# Lightpack6_0L.net
KiCad netlist of a schematic drawn in EAGLE
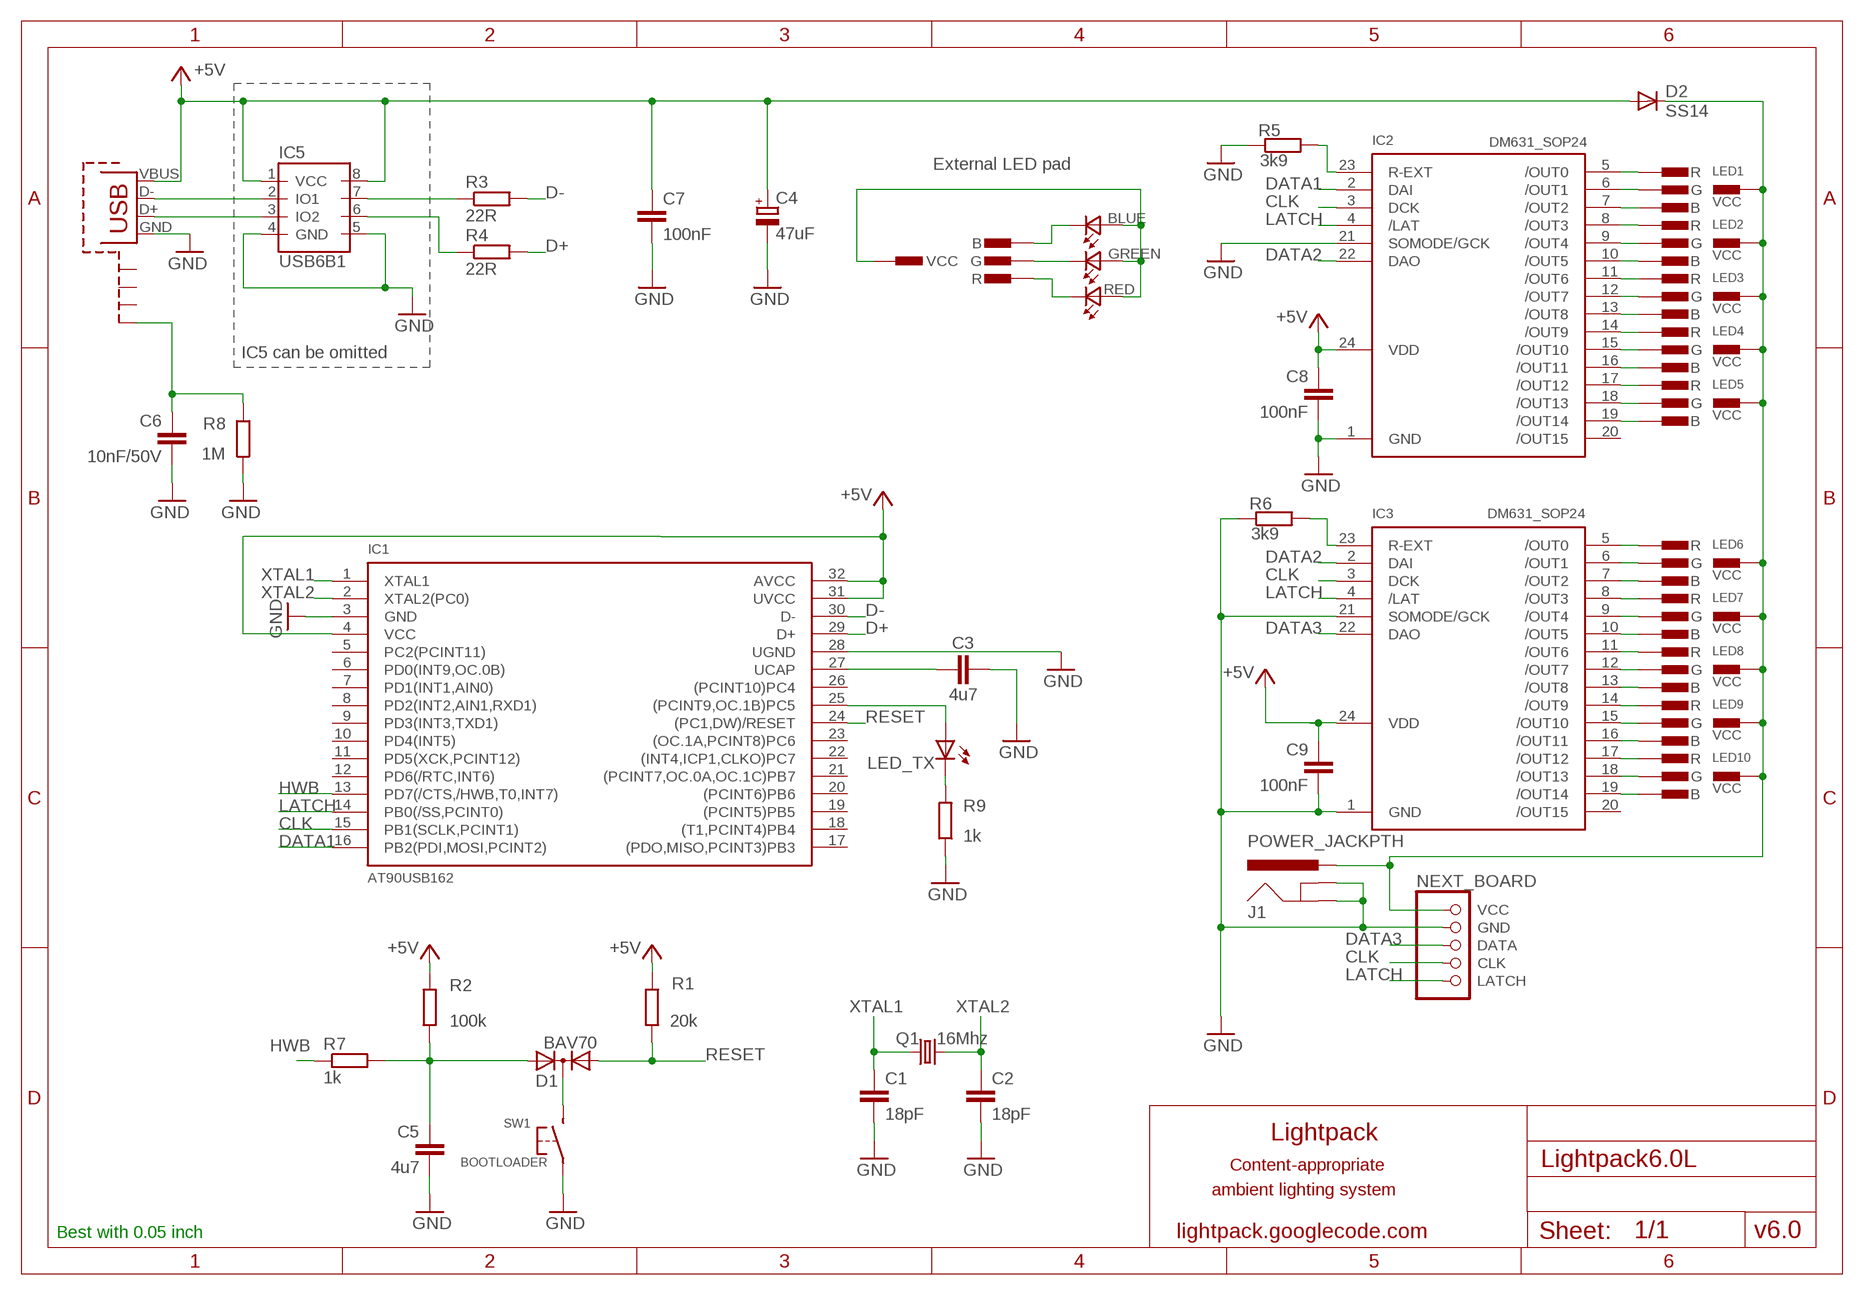
[diagram p0: schematic, sheet 1]

(export (version "E")
  (design (tool "Eeschema 10.0.6"))
  (components
    (comp (ref "C1")
      (value "18pF")
      (footprint "eagle-import:C1206")
      (libsource (lib "eagle-import") (part "C-EUC1206"))
    )
    (comp (ref "C2")
      (value "18pF")
      (footprint "eagle-import:C1206")
      (libsource (lib "eagle-import") (part "C-EUC1206"))
    )
    (comp (ref "C3")
      (value "4u7")
      (footprint "eagle-import:C1206")
      (libsource (lib "eagle-import") (part "C-EUC1206"))
    )
    (comp (ref "C4")
      (value "47uF")
      (footprint "eagle-import:D_7343-31W")
      (libsource (lib "eagle-import") (part "CPOL-EUD/7343-31W"))
    )
    (comp (ref "C5")
      (value "4u7")
      (footprint "eagle-import:C1206")
      (libsource (lib "eagle-import") (part "C-EUC1206"))
    )
    (comp (ref "C6")
      (value "10nF/50V")
      (footprint "eagle-import:C1206")
      (libsource (lib "eagle-import") (part "C-EUC1206"))
    )
    (comp (ref "C7")
      (value "100nF")
      (footprint "eagle-import:C1206")
      (libsource (lib "eagle-import") (part "C-EUC1206"))
    )
    (comp (ref "C8")
      (value "100nF")
      (footprint "eagle-import:C1206")
      (libsource (lib "eagle-import") (part "C-EUC1206"))
    )
    (comp (ref "C9")
      (value "100nF")
      (footprint "eagle-import:C1206")
      (libsource (lib "eagle-import") (part "C-EUC1206"))
    )
    (comp (ref "D1")
      (value "BAV70")
      (footprint "eagle-import:SOT23")
      (libsource (lib "eagle-import") (part "DIODE-2AC|CASOT23"))
    )
    (comp (ref "D2")
      (value "SS14")
      (footprint "eagle-import:SMB")
      (libsource (lib "eagle-import") (part "DIODE-SMB"))
    )
    (comp (ref "EXT_LED")
      (value "TOPLED-3RF-W2SA50TS")
      (footprint "eagle-import:LP2C63-ST-RGB-SR0")
      (libsource (lib "eagle-import") (part "TOPLED-3RF-W2SA50TS"))
    )
    (comp (ref "IC1")
      (value "AT90USB162")
      (footprint "eagle-import:TQFP32")
      (libsource (lib "eagle-import") (part "AT90USB162"))
    )
    (comp (ref "IC2")
      (value "DM631_SOP24")
      (footprint "eagle-import:SOP24-300-1.27")
      (libsource (lib "eagle-import") (part "DM631_SOP24"))
    )
    (comp (ref "IC3")
      (value "DM631_SOP24")
      (footprint "eagle-import:SOP24-300-1.27")
      (libsource (lib "eagle-import") (part "DM631_SOP24"))
    )
    (comp (ref "IC5")
      (value "USB6B1")
      (footprint "eagle-import:SO08")
      (libsource (lib "eagle-import") (part "USB6B1"))
    )
    (comp (ref "J1")
      (value "POWER_JACKPTH")
      (footprint "eagle-import:POWER_JACK_PTH")
      (libsource (lib "eagle-import") (part "POWER_JACKPTH"))
    )
    (comp (ref "LED1")
      (value "CON-RGB-LED")
      (footprint "eagle-import:CON-RGB-LED")
      (libsource (lib "eagle-import") (part "CON-RGB-LED"))
    )
    (comp (ref "LED2")
      (value "CON-RGB-LED")
      (footprint "eagle-import:CON-RGB-LED")
      (libsource (lib "eagle-import") (part "CON-RGB-LED"))
    )
    (comp (ref "LED3")
      (value "CON-RGB-LED")
      (footprint "eagle-import:CON-RGB-LED")
      (libsource (lib "eagle-import") (part "CON-RGB-LED"))
    )
    (comp (ref "LED4")
      (value "CON-RGB-LEDVCC-INDENT")
      (footprint "eagle-import:CON-RGB-LED-WITH-VCC-INDENT")
      (libsource (lib "eagle-import") (part "CON-RGB-LEDVCC-INDENT"))
    )
    (comp (ref "LED5")
      (value "CON-RGB-LEDVCC-INDENT")
      (footprint "eagle-import:CON-RGB-LED-WITH-VCC-INDENT")
      (libsource (lib "eagle-import") (part "CON-RGB-LEDVCC-INDENT"))
    )
    (comp (ref "LED6")
      (value "CON-RGB-LED")
      (footprint "eagle-import:CON-RGB-LED")
      (libsource (lib "eagle-import") (part "CON-RGB-LED"))
    )
    (comp (ref "LED7")
      (value "CON-RGB-LED")
      (footprint "eagle-import:CON-RGB-LED")
      (libsource (lib "eagle-import") (part "CON-RGB-LED"))
    )
    (comp (ref "LED8")
      (value "CON-RGB-LED")
      (footprint "eagle-import:CON-RGB-LED")
      (libsource (lib "eagle-import") (part "CON-RGB-LED"))
    )
    (comp (ref "LED9")
      (value "CON-RGB-LED")
      (footprint "eagle-import:CON-RGB-LED")
      (libsource (lib "eagle-import") (part "CON-RGB-LED"))
    )
    (comp (ref "LED10")
      (value "CON-RGB-LED")
      (footprint "eagle-import:CON-RGB-LED")
      (libsource (lib "eagle-import") (part "CON-RGB-LED"))
    )
    (comp (ref "LED12")
      (value "CON-RGB-LED\"")
      (footprint "eagle-import:CON-RGB-LED")
      (libsource (lib "eagle-import") (part "CON-RGB-LED{dblquote}"))
    )
    (comp (ref "LED_TX")
      (value "GREEN")
      (footprint "eagle-import:CHIPLED_0805")
      (libsource (lib "eagle-import") (part "LEDCHIPLED_0805"))
    )
    (comp (ref "NEXT_BOARD")
      (value "LED_DRIVER_BOARD")
      (footprint "eagle-import:DATA-CLK-LATCH")
      (libsource (lib "eagle-import") (part "LED_DRIVER_BOARD"))
    )
    (comp (ref "Q1")
      (value "16Mhz")
      (footprint "eagle-import:HC49UP")
      (libsource (lib "eagle-import") (part "CRYSTALHC49UP"))
    )
    (comp (ref "R1")
      (value "20k")
      (footprint "eagle-import:R1206")
      (libsource (lib "eagle-import") (part "R-EU_R1206"))
    )
    (comp (ref "R2")
      (value "100k")
      (footprint "eagle-import:R1206")
      (libsource (lib "eagle-import") (part "R-EU_R1206_2"))
    )
    (comp (ref "R3")
      (value "22R")
      (footprint "eagle-import:R1206")
      (libsource (lib "eagle-import") (part "rcl_R-EU_R1206"))
    )
    (comp (ref "R4")
      (value "22R")
      (footprint "eagle-import:R1206")
      (libsource (lib "eagle-import") (part "rcl_R-EU_R1206"))
    )
    (comp (ref "R5")
      (value "3k9")
      (footprint "eagle-import:R1206")
      (libsource (lib "eagle-import") (part "R-EU_R1206"))
    )
    (comp (ref "R6")
      (value "3k9")
      (footprint "eagle-import:R1206")
      (libsource (lib "eagle-import") (part "R-EU_R1206"))
    )
    (comp (ref "R7")
      (value "1k")
      (footprint "eagle-import:R1206")
      (libsource (lib "eagle-import") (part "rcl_R-EU_R1206"))
    )
    (comp (ref "R8")
      (value "1M")
      (footprint "eagle-import:R1206")
      (libsource (lib "eagle-import") (part "rcl_R-EU_R1206"))
    )
    (comp (ref "R9")
      (value "1k")
      (footprint "eagle-import:R1206")
      (libsource (lib "eagle-import") (part "rcl_R-EU_R1206"))
    )
    (comp (ref "SW1")
      (value "BOOTLOADER")
      (footprint "eagle-import:BUTTON-SMD")
      (libsource (lib "eagle-import") (part "BUTTON"))
    )
    (comp (ref "X1")
      (value "USB-MB-S")
      (footprint "eagle-import:USB-MB-S")
      (libsource (lib "eagle-import") (part "USB-MB-S"))
    )
  )
  (nets
    (net (code "1") (name "+5V") (class "Default")
      (node (ref "C4") (pin "+") (pinfunction "+_+") (pintype "passive"))
      (node (ref "C7") (pin "1") (pinfunction "1_1") (pintype "passive"))
      (node (ref "C8") (pin "1") (pinfunction "1_1") (pintype "passive"))
      (node (ref "C9") (pin "1") (pinfunction "1_1") (pintype "passive"))
      (node (ref "D2") (pin "A") (pinfunction "A_A") (pintype "passive"))
      (node (ref "IC1") (pin "31") (pinfunction "UVCC_31") (pintype "bidirectional"))
      (node (ref "IC1") (pin "32") (pinfunction "AVCC_32") (pintype "bidirectional"))
      (node (ref "IC1") (pin "4") (pinfunction "VCC_4") (pintype "bidirectional"))
      (node (ref "IC2") (pin "24") (pinfunction "VDD_24") (pintype "bidirectional"))
      (node (ref "IC3") (pin "24") (pinfunction "VDD_24") (pintype "bidirectional"))
      (node (ref "IC5") (pin "1") (pinfunction "VCC_1") (pintype "power_in"))
      (node (ref "IC5") (pin "8") (pinfunction "VCC_8") (pintype "power_in"))
      (node (ref "R1") (pin "2") (pinfunction "2_2") (pintype "passive"))
      (node (ref "R2") (pin "1") (pinfunction "2_1") (pintype "passive"))
      (node (ref "X1") (pin "VBUS") (pinfunction "VBUS_VBUS") (pintype "bidirectional"))
    )
    (net (code "2") (name "/CLK") (class "Default")
      (node (ref "IC1") (pin "15") (pinfunction "PB1(SCLK,PCINT1)_15") (pintype "bidirectional"))
      (node (ref "IC2") (pin "3") (pinfunction "DCK_3") (pintype "bidirectional"))
      (node (ref "IC3") (pin "3") (pinfunction "DCK_3") (pintype "bidirectional"))
      (node (ref "NEXT_BOARD") (pin "CLK") (pinfunction "CLK_CLK") (pintype "passive"))
    )
    (net (code "3") (name "/D+") (class "Default")
      (node (ref "IC1") (pin "29") (pinfunction "D+_29") (pintype "bidirectional"))
      (node (ref "R4") (pin "2") (pinfunction "2_2") (pintype "passive"))
    )
    (net (code "4") (name "/D-") (class "Default")
      (node (ref "IC1") (pin "30") (pinfunction "D-_30") (pintype "bidirectional"))
      (node (ref "R3") (pin "2") (pinfunction "2_2") (pintype "passive"))
    )
    (net (code "5") (name "/DATA1") (class "Default")
      (node (ref "IC1") (pin "16") (pinfunction "PB2(PDI,MOSI,PCINT2)_16") (pintype "bidirectional"))
      (node (ref "IC2") (pin "2") (pinfunction "DAI_2") (pintype "bidirectional"))
    )
    (net (code "6") (name "/DATA2") (class "Default")
      (node (ref "IC2") (pin "22") (pinfunction "DAO_22") (pintype "bidirectional"))
      (node (ref "IC3") (pin "2") (pinfunction "DAI_2") (pintype "bidirectional"))
    )
    (net (code "7") (name "/DATA3") (class "Default")
      (node (ref "IC3") (pin "22") (pinfunction "DAO_22") (pintype "bidirectional"))
      (node (ref "NEXT_BOARD") (pin "DATA") (pinfunction "DATA_DATA") (pintype "passive"))
    )
    (net (code "8") (name "/HWB") (class "Default")
      (node (ref "IC1") (pin "13") (pinfunction "PD7(/CTS,/HWB,T0,INT7)_13") (pintype "bidirectional"))
      (node (ref "R7") (pin "1") (pinfunction "1_1") (pintype "passive"))
    )
    (net (code "9") (name "/LATCH") (class "Default")
      (node (ref "IC1") (pin "14") (pinfunction "PB0(/SS,PCINT0)_14") (pintype "bidirectional"))
      (node (ref "IC2") (pin "4") (pinfunction "/LAT_4") (pintype "bidirectional"))
      (node (ref "IC3") (pin "4") (pinfunction "/LAT_4") (pintype "bidirectional"))
      (node (ref "NEXT_BOARD") (pin "LATCH") (pinfunction "LATCH_LATCH") (pintype "passive"))
    )
    (net (code "10") (name "/RESET") (class "Default")
      (node (ref "D1") (pin "1") (pinfunction "A1_1") (pintype "passive"))
      (node (ref "IC1") (pin "24") (pinfunction "(PC1,DW)/RESET_24") (pintype "bidirectional"))
      (node (ref "R1") (pin "1") (pinfunction "1_1") (pintype "passive"))
    )
    (net (code "11") (name "/XTAL1") (class "Default")
      (node (ref "C1") (pin "1") (pinfunction "1_1") (pintype "passive"))
      (node (ref "IC1") (pin "1") (pinfunction "XTAL1_1") (pintype "bidirectional"))
      (node (ref "Q1") (pin "1") (pinfunction "1_1") (pintype "passive"))
    )
    (net (code "12") (name "/XTAL2") (class "Default")
      (node (ref "C2") (pin "1") (pinfunction "1_1") (pintype "passive"))
      (node (ref "IC1") (pin "2") (pinfunction "XTAL2(PC0)_2") (pintype "bidirectional"))
      (node (ref "Q1") (pin "2") (pinfunction "2_2") (pintype "passive"))
    )
    (net (code "13") (name "GND") (class "Default")
      (node (ref "C1") (pin "2") (pinfunction "2_2") (pintype "passive"))
      (node (ref "C2") (pin "2") (pinfunction "2_2") (pintype "passive"))
      (node (ref "C3") (pin "1") (pinfunction "1_1") (pintype "passive"))
      (node (ref "C4") (pin "-") (pinfunction "-_-") (pintype "passive"))
      (node (ref "C5") (pin "2") (pinfunction "2_2") (pintype "passive"))
      (node (ref "C6") (pin "2") (pinfunction "2_2") (pintype "passive"))
      (node (ref "C7") (pin "2") (pinfunction "2_2") (pintype "passive"))
      (node (ref "C8") (pin "2") (pinfunction "2_2") (pintype "passive"))
      (node (ref "C9") (pin "2") (pinfunction "2_2") (pintype "passive"))
      (node (ref "IC1") (pin "28") (pinfunction "UGND_28") (pintype "bidirectional"))
      (node (ref "IC1") (pin "3") (pinfunction "GND_3") (pintype "bidirectional"))
      (node (ref "IC2") (pin "1") (pinfunction "GND_1") (pintype "bidirectional"))
      (node (ref "IC2") (pin "21") (pinfunction "SOMODE/GCK_21") (pintype "bidirectional"))
      (node (ref "IC3") (pin "1") (pinfunction "GND_1") (pintype "bidirectional"))
      (node (ref "IC3") (pin "21") (pinfunction "SOMODE/GCK_21") (pintype "bidirectional"))
      (node (ref "IC5") (pin "4") (pinfunction "GND_4") (pintype "power_in"))
      (node (ref "IC5") (pin "5") (pinfunction "GND_5") (pintype "power_in"))
      (node (ref "J1") (pin "GND") (pinfunction "GND_GND") (pintype "bidirectional"))
      (node (ref "J1") (pin "GNDBREAK") (pinfunction "GNDBREAK_GNDBREAK") (pintype "bidirectional"))
      (node (ref "NEXT_BOARD") (pin "GND") (pinfunction "GND_GND") (pintype "passive"))
      (node (ref "R5") (pin "1") (pinfunction "1_1") (pintype "passive"))
      (node (ref "R6") (pin "1") (pinfunction "1_1") (pintype "passive"))
      (node (ref "R8") (pin "1") (pinfunction "1_1") (pintype "passive"))
      (node (ref "R9") (pin "1") (pinfunction "1_1") (pintype "passive"))
      (node (ref "SW1") (pin "1") (pinfunction "1_1") (pintype "passive"))
      (node (ref "X1") (pin "GND") (pinfunction "GND_GND") (pintype "bidirectional"))
    )
    (net (code "14") (name "Net-(C6-Pad1)") (class "Default")
      (node (ref "C6") (pin "1") (pinfunction "1_1") (pintype "passive"))
      (node (ref "R8") (pin "2") (pinfunction "2_2") (pintype "passive"))
      (node (ref "X1") (pin "SHIELD4") (pinfunction "SHIELD4_SHIELD4") (pintype "bidirectional"))
    )
    (net (code "15") (name "Net-(D1-A2)") (class "Default")
      (node (ref "C5") (pin "1") (pinfunction "1_1") (pintype "passive"))
      (node (ref "D1") (pin "2") (pinfunction "A2_2") (pintype "passive"))
      (node (ref "R2") (pin "2") (pinfunction "1_2") (pintype "passive"))
      (node (ref "R7") (pin "2") (pinfunction "2_2") (pintype "passive"))
    )
    (net (code "16") (name "Net-(D1-C)") (class "Default")
      (node (ref "D1") (pin "3") (pinfunction "C_3") (pintype "passive"))
      (node (ref "SW1") (pin "2") (pinfunction "2_2") (pintype "passive"))
    )
    (net (code "17") (name "Net-(D2-PadC)") (class "Default")
      (node (ref "D2") (pin "C") (pinfunction "C_C") (pintype "passive"))
      (node (ref "J1") (pin "PWR") (pinfunction "PWR_PWR") (pintype "bidirectional"))
      (node (ref "LED1") (pin "VCC") (pinfunction "VCC_VCC") (pintype "bidirectional"))
      (node (ref "LED10") (pin "VCC") (pinfunction "VCC_VCC") (pintype "bidirectional"))
      (node (ref "LED2") (pin "VCC") (pinfunction "VCC_VCC") (pintype "bidirectional"))
      (node (ref "LED3") (pin "VCC") (pinfunction "VCC_VCC") (pintype "bidirectional"))
      (node (ref "LED4") (pin "VCC") (pinfunction "VCC_VCC") (pintype "bidirectional"))
      (node (ref "LED5") (pin "VCC") (pinfunction "VCC_VCC") (pintype "bidirectional"))
      (node (ref "LED6") (pin "VCC") (pinfunction "VCC_VCC") (pintype "bidirectional"))
      (node (ref "LED7") (pin "VCC") (pinfunction "VCC_VCC") (pintype "bidirectional"))
      (node (ref "LED8") (pin "VCC") (pinfunction "VCC_VCC") (pintype "bidirectional"))
      (node (ref "LED9") (pin "VCC") (pinfunction "VCC_VCC") (pintype "bidirectional"))
      (node (ref "NEXT_BOARD") (pin "VCC") (pinfunction "VCC_VCC") (pintype "passive"))
    )
    (net (code "18") (name "Net-(EXT_LED-PadBLUE)") (class "Default")
      (node (ref "EXT_LED") (pin "BLUE") (pinfunction "BLUE_BLUE") (pintype "passive"))
      (node (ref "EXT_LED") (pin "GREEN") (pinfunction "GREEN_GREEN") (pintype "passive"))
      (node (ref "EXT_LED") (pin "RED") (pinfunction "RED_RED") (pintype "passive"))
      (node (ref "LED12") (pin "VCC") (pinfunction "VCC_VCC") (pintype "bidirectional"))
    )
    (net (code "19") (name "Net-(EXT_LED-PadCBLUE)") (class "Default")
      (node (ref "EXT_LED") (pin "CBLUE") (pinfunction "CBLUE_CBLUE") (pintype "passive"))
      (node (ref "LED12") (pin "B") (pinfunction "B_B") (pintype "bidirectional"))
    )
    (net (code "20") (name "Net-(EXT_LED-PadCGREEN)") (class "Default")
      (node (ref "EXT_LED") (pin "CGREEN") (pinfunction "CGREEN_CGREEN") (pintype "passive"))
      (node (ref "LED12") (pin "G") (pinfunction "G_G") (pintype "bidirectional"))
    )
    (net (code "21") (name "Net-(EXT_LED-PadCRED)") (class "Default")
      (node (ref "EXT_LED") (pin "CRED") (pinfunction "CRED_CRED") (pintype "passive"))
      (node (ref "LED12") (pin "R") (pinfunction "R_R") (pintype "bidirectional"))
    )
    (net (code "22") (name "Net-(IC1-(PCINT9,OC.1B)PC5)") (class "Default")
      (node (ref "IC1") (pin "25") (pinfunction "(PCINT9,OC.1B)PC5_25") (pintype "bidirectional"))
      (node (ref "LED_TX") (pin "A") (pinfunction "A_A") (pintype "passive"))
    )
    (net (code "23") (name "Net-(IC1-UCAP)") (class "Default")
      (node (ref "C3") (pin "2") (pinfunction "2_2") (pintype "passive"))
      (node (ref "IC1") (pin "27") (pinfunction "UCAP_27") (pintype "bidirectional"))
    )
    (net (code "24") (name "Net-(IC2-R-EXT)") (class "Default")
      (node (ref "IC2") (pin "23") (pinfunction "R-EXT_23") (pintype "bidirectional"))
      (node (ref "R5") (pin "2") (pinfunction "2_2") (pintype "passive"))
    )
    (net (code "25") (name "Net-(IC2-{slash}OUT0)") (class "Default")
      (node (ref "IC2") (pin "5") (pinfunction "/OUT0_5") (pintype "bidirectional"))
      (node (ref "LED1") (pin "R") (pinfunction "R_R") (pintype "bidirectional"))
    )
    (net (code "26") (name "Net-(IC2-{slash}OUT1)") (class "Default")
      (node (ref "IC2") (pin "6") (pinfunction "/OUT1_6") (pintype "bidirectional"))
      (node (ref "LED1") (pin "G") (pinfunction "G_G") (pintype "bidirectional"))
    )
    (net (code "27") (name "Net-(IC2-{slash}OUT2)") (class "Default")
      (node (ref "IC2") (pin "7") (pinfunction "/OUT2_7") (pintype "bidirectional"))
      (node (ref "LED1") (pin "B") (pinfunction "B_B") (pintype "bidirectional"))
    )
    (net (code "28") (name "Net-(IC2-{slash}OUT3)") (class "Default")
      (node (ref "IC2") (pin "8") (pinfunction "/OUT3_8") (pintype "bidirectional"))
      (node (ref "LED2") (pin "R") (pinfunction "R_R") (pintype "bidirectional"))
    )
    (net (code "29") (name "Net-(IC2-{slash}OUT4)") (class "Default")
      (node (ref "IC2") (pin "9") (pinfunction "/OUT4_9") (pintype "bidirectional"))
      (node (ref "LED2") (pin "G") (pinfunction "G_G") (pintype "bidirectional"))
    )
    (net (code "30") (name "Net-(IC2-{slash}OUT5)") (class "Default")
      (node (ref "IC2") (pin "10") (pinfunction "/OUT5_10") (pintype "bidirectional"))
      (node (ref "LED2") (pin "B") (pinfunction "B_B") (pintype "bidirectional"))
    )
    (net (code "31") (name "Net-(IC2-{slash}OUT6)") (class "Default")
      (node (ref "IC2") (pin "11") (pinfunction "/OUT6_11") (pintype "bidirectional"))
      (node (ref "LED3") (pin "R") (pinfunction "R_R") (pintype "bidirectional"))
    )
    (net (code "32") (name "Net-(IC2-{slash}OUT7)") (class "Default")
      (node (ref "IC2") (pin "12") (pinfunction "/OUT7_12") (pintype "bidirectional"))
      (node (ref "LED3") (pin "G") (pinfunction "G_G") (pintype "bidirectional"))
    )
    (net (code "33") (name "Net-(IC2-{slash}OUT8)") (class "Default")
      (node (ref "IC2") (pin "13") (pinfunction "/OUT8_13") (pintype "bidirectional"))
      (node (ref "LED3") (pin "B") (pinfunction "B_B") (pintype "bidirectional"))
    )
    (net (code "34") (name "Net-(IC2-{slash}OUT9)") (class "Default")
      (node (ref "IC2") (pin "14") (pinfunction "/OUT9_14") (pintype "bidirectional"))
      (node (ref "LED4") (pin "R") (pinfunction "R_R") (pintype "bidirectional"))
    )
    (net (code "35") (name "Net-(IC2-{slash}OUT10)") (class "Default")
      (node (ref "IC2") (pin "15") (pinfunction "/OUT10_15") (pintype "bidirectional"))
      (node (ref "LED4") (pin "G") (pinfunction "G_G") (pintype "bidirectional"))
    )
    (net (code "36") (name "Net-(IC2-{slash}OUT11)") (class "Default")
      (node (ref "IC2") (pin "16") (pinfunction "/OUT11_16") (pintype "bidirectional"))
      (node (ref "LED4") (pin "B") (pinfunction "B_B") (pintype "bidirectional"))
    )
    (net (code "37") (name "Net-(IC2-{slash}OUT12)") (class "Default")
      (node (ref "IC2") (pin "17") (pinfunction "/OUT12_17") (pintype "bidirectional"))
      (node (ref "LED5") (pin "R") (pinfunction "R_R") (pintype "bidirectional"))
    )
    (net (code "38") (name "Net-(IC2-{slash}OUT13)") (class "Default")
      (node (ref "IC2") (pin "18") (pinfunction "/OUT13_18") (pintype "bidirectional"))
      (node (ref "LED5") (pin "G") (pinfunction "G_G") (pintype "bidirectional"))
    )
    (net (code "39") (name "Net-(IC2-{slash}OUT14)") (class "Default")
      (node (ref "IC2") (pin "19") (pinfunction "/OUT14_19") (pintype "bidirectional"))
      (node (ref "LED5") (pin "B") (pinfunction "B_B") (pintype "bidirectional"))
    )
    (net (code "40") (name "Net-(IC3-R-EXT)") (class "Default")
      (node (ref "IC3") (pin "23") (pinfunction "R-EXT_23") (pintype "bidirectional"))
      (node (ref "R6") (pin "2") (pinfunction "2_2") (pintype "passive"))
    )
    (net (code "41") (name "Net-(IC3-{slash}OUT0)") (class "Default")
      (node (ref "IC3") (pin "5") (pinfunction "/OUT0_5") (pintype "bidirectional"))
      (node (ref "LED6") (pin "R") (pinfunction "R_R") (pintype "bidirectional"))
    )
    (net (code "42") (name "Net-(IC3-{slash}OUT1)") (class "Default")
      (node (ref "IC3") (pin "6") (pinfunction "/OUT1_6") (pintype "bidirectional"))
      (node (ref "LED6") (pin "G") (pinfunction "G_G") (pintype "bidirectional"))
    )
    (net (code "43") (name "Net-(IC3-{slash}OUT2)") (class "Default")
      (node (ref "IC3") (pin "7") (pinfunction "/OUT2_7") (pintype "bidirectional"))
      (node (ref "LED6") (pin "B") (pinfunction "B_B") (pintype "bidirectional"))
    )
    (net (code "44") (name "Net-(IC3-{slash}OUT3)") (class "Default")
      (node (ref "IC3") (pin "8") (pinfunction "/OUT3_8") (pintype "bidirectional"))
      (node (ref "LED7") (pin "R") (pinfunction "R_R") (pintype "bidirectional"))
    )
    (net (code "45") (name "Net-(IC3-{slash}OUT4)") (class "Default")
      (node (ref "IC3") (pin "9") (pinfunction "/OUT4_9") (pintype "bidirectional"))
      (node (ref "LED7") (pin "G") (pinfunction "G_G") (pintype "bidirectional"))
    )
    (net (code "46") (name "Net-(IC3-{slash}OUT5)") (class "Default")
      (node (ref "IC3") (pin "10") (pinfunction "/OUT5_10") (pintype "bidirectional"))
      (node (ref "LED7") (pin "B") (pinfunction "B_B") (pintype "bidirectional"))
    )
    (net (code "47") (name "Net-(IC3-{slash}OUT6)") (class "Default")
      (node (ref "IC3") (pin "11") (pinfunction "/OUT6_11") (pintype "bidirectional"))
      (node (ref "LED8") (pin "R") (pinfunction "R_R") (pintype "bidirectional"))
    )
    (net (code "48") (name "Net-(IC3-{slash}OUT7)") (class "Default")
      (node (ref "IC3") (pin "12") (pinfunction "/OUT7_12") (pintype "bidirectional"))
      (node (ref "LED8") (pin "G") (pinfunction "G_G") (pintype "bidirectional"))
    )
    (net (code "49") (name "Net-(IC3-{slash}OUT8)") (class "Default")
      (node (ref "IC3") (pin "13") (pinfunction "/OUT8_13") (pintype "bidirectional"))
      (node (ref "LED8") (pin "B") (pinfunction "B_B") (pintype "bidirectional"))
    )
    (net (code "50") (name "Net-(IC3-{slash}OUT9)") (class "Default")
      (node (ref "IC3") (pin "14") (pinfunction "/OUT9_14") (pintype "bidirectional"))
      (node (ref "LED9") (pin "R") (pinfunction "R_R") (pintype "bidirectional"))
    )
    (net (code "51") (name "Net-(IC3-{slash}OUT10)") (class "Default")
      (node (ref "IC3") (pin "15") (pinfunction "/OUT10_15") (pintype "bidirectional"))
      (node (ref "LED9") (pin "G") (pinfunction "G_G") (pintype "bidirectional"))
    )
    (net (code "52") (name "Net-(IC3-{slash}OUT11)") (class "Default")
      (node (ref "IC3") (pin "16") (pinfunction "/OUT11_16") (pintype "bidirectional"))
      (node (ref "LED9") (pin "B") (pinfunction "B_B") (pintype "bidirectional"))
    )
    (net (code "53") (name "Net-(IC3-{slash}OUT12)") (class "Default")
      (node (ref "IC3") (pin "17") (pinfunction "/OUT12_17") (pintype "bidirectional"))
      (node (ref "LED10") (pin "R") (pinfunction "R_R") (pintype "bidirectional"))
    )
    (net (code "54") (name "Net-(IC3-{slash}OUT13)") (class "Default")
      (node (ref "IC3") (pin "18") (pinfunction "/OUT13_18") (pintype "bidirectional"))
      (node (ref "LED10") (pin "G") (pinfunction "G_G") (pintype "bidirectional"))
    )
    (net (code "55") (name "Net-(IC3-{slash}OUT14)") (class "Default")
      (node (ref "IC3") (pin "19") (pinfunction "/OUT14_19") (pintype "bidirectional"))
      (node (ref "LED10") (pin "B") (pinfunction "B_B") (pintype "bidirectional"))
    )
    (net (code "56") (name "Net-(IC5-IO1-Pad2)") (class "Default")
      (node (ref "IC5") (pin "2") (pinfunction "IO1_2") (pintype "bidirectional"))
      (node (ref "X1") (pin "D-") (pinfunction "D-_D-") (pintype "bidirectional"))
    )
    (net (code "57") (name "Net-(IC5-IO1-Pad7)") (class "Default")
      (node (ref "IC5") (pin "7") (pinfunction "IO1_7") (pintype "bidirectional"))
      (node (ref "R3") (pin "1") (pinfunction "1_1") (pintype "passive"))
    )
    (net (code "58") (name "Net-(IC5-IO2-Pad3)") (class "Default")
      (node (ref "IC5") (pin "3") (pinfunction "IO2_3") (pintype "bidirectional"))
      (node (ref "X1") (pin "D+") (pinfunction "D+_D+") (pintype "bidirectional"))
    )
    (net (code "59") (name "Net-(IC5-IO2-Pad6)") (class "Default")
      (node (ref "IC5") (pin "6") (pinfunction "IO2_6") (pintype "bidirectional"))
      (node (ref "R4") (pin "1") (pinfunction "1_1") (pintype "passive"))
    )
    (net (code "60") (name "Net-(LED_TX-PadC)") (class "Default")
      (node (ref "LED_TX") (pin "C") (pinfunction "C_C") (pintype "passive"))
      (node (ref "R9") (pin "2") (pinfunction "2_2") (pintype "passive"))
    )
    (net (code "61") (name "unconnected-(IC1-(INT4,ICP1,CLKO)PC7-Pad22)") (class "Default")
      (node (ref "IC1") (pin "22") (pinfunction "(INT4,ICP1,CLKO)PC7_22") (pintype "bidirectional"))
    )
    (net (code "62") (name "unconnected-(IC1-(OC.1A,PCINT8)PC6-Pad23)") (class "Default")
      (node (ref "IC1") (pin "23") (pinfunction "(OC.1A,PCINT8)PC6_23") (pintype "bidirectional"))
    )
    (net (code "63") (name "unconnected-(IC1-(PCINT5)PB5-Pad19)") (class "Default")
      (node (ref "IC1") (pin "19") (pinfunction "(PCINT5)PB5_19") (pintype "bidirectional"))
    )
    (net (code "64") (name "unconnected-(IC1-(PCINT6)PB6-Pad20)") (class "Default")
      (node (ref "IC1") (pin "20") (pinfunction "(PCINT6)PB6_20") (pintype "bidirectional"))
    )
    (net (code "65") (name "unconnected-(IC1-(PCINT7,OC.0A,OC.1C)PB7-Pad21)") (class "Default")
      (node (ref "IC1") (pin "21") (pinfunction "(PCINT7,OC.0A,OC.1C)PB7_21") (pintype "bidirectional"))
    )
    (net (code "66") (name "unconnected-(IC1-(PCINT10)PC4-Pad26)") (class "Default")
      (node (ref "IC1") (pin "26") (pinfunction "(PCINT10)PC4_26") (pintype "bidirectional"))
    )
    (net (code "67") (name "unconnected-(IC1-(PDO,MISO,PCINT3)PB3-Pad17)") (class "Default")
      (node (ref "IC1") (pin "17") (pinfunction "(PDO,MISO,PCINT3)PB3_17") (pintype "bidirectional"))
    )
    (net (code "68") (name "unconnected-(IC1-(T1,PCINT4)PB4-Pad18)") (class "Default")
      (node (ref "IC1") (pin "18") (pinfunction "(T1,PCINT4)PB4_18") (pintype "bidirectional"))
    )
    (net (code "69") (name "unconnected-(IC1-PC2(PCINT11)-Pad5)") (class "Default")
      (node (ref "IC1") (pin "5") (pinfunction "PC2(PCINT11)_5") (pintype "bidirectional"))
    )
    (net (code "70") (name "unconnected-(IC1-PD0(INT9,OC.0B)-Pad6)") (class "Default")
      (node (ref "IC1") (pin "6") (pinfunction "PD0(INT9,OC.0B)_6") (pintype "bidirectional"))
    )
    (net (code "71") (name "unconnected-(IC1-PD1(INT1,AIN0)-Pad7)") (class "Default")
      (node (ref "IC1") (pin "7") (pinfunction "PD1(INT1,AIN0)_7") (pintype "bidirectional"))
    )
    (net (code "72") (name "unconnected-(IC1-PD2(INT2,AIN1,RXD1)-Pad8)") (class "Default")
      (node (ref "IC1") (pin "8") (pinfunction "PD2(INT2,AIN1,RXD1)_8") (pintype "bidirectional"))
    )
    (net (code "73") (name "unconnected-(IC1-PD3(INT3,TXD1)-Pad9)") (class "Default")
      (node (ref "IC1") (pin "9") (pinfunction "PD3(INT3,TXD1)_9") (pintype "bidirectional"))
    )
    (net (code "74") (name "unconnected-(IC1-PD4(INT5)-Pad10)") (class "Default")
      (node (ref "IC1") (pin "10") (pinfunction "PD4(INT5)_10") (pintype "bidirectional"))
    )
    (net (code "75") (name "unconnected-(IC1-PD5(XCK,PCINT12)-Pad11)") (class "Default")
      (node (ref "IC1") (pin "11") (pinfunction "PD5(XCK,PCINT12)_11") (pintype "bidirectional"))
    )
    (net (code "76") (name "unconnected-(IC1-PD6({slash}RTC,INT6)-Pad12)") (class "Default")
      (node (ref "IC1") (pin "12") (pinfunction "PD6(/RTC,INT6)_12") (pintype "bidirectional"))
    )
    (net (code "77") (name "unconnected-(IC2-{slash}OUT15-Pad20)") (class "Default")
      (node (ref "IC2") (pin "20") (pinfunction "/OUT15_20") (pintype "bidirectional"))
    )
    (net (code "78") (name "unconnected-(IC3-{slash}OUT15-Pad20)") (class "Default")
      (node (ref "IC3") (pin "20") (pinfunction "/OUT15_20") (pintype "bidirectional"))
    )
    (net (code "79") (name "unconnected-(X1-PadSHIELD1)") (class "Default")
      (node (ref "X1") (pin "SHIELD1") (pinfunction "SHIELD1_SHIELD1") (pintype "bidirectional"))
    )
    (net (code "80") (name "unconnected-(X1-PadSHIELD2)") (class "Default")
      (node (ref "X1") (pin "SHIELD2") (pinfunction "SHIELD2_SHIELD2") (pintype "bidirectional"))
    )
    (net (code "81") (name "unconnected-(X1-PadSHIELD3)") (class "Default")
      (node (ref "X1") (pin "SHIELD3") (pinfunction "SHIELD3_SHIELD3") (pintype "bidirectional"))
    )
  )
)
